# Hands_free_Motordrive_V1.net
KiCad netlist of a schematic drawn in Altium Designer
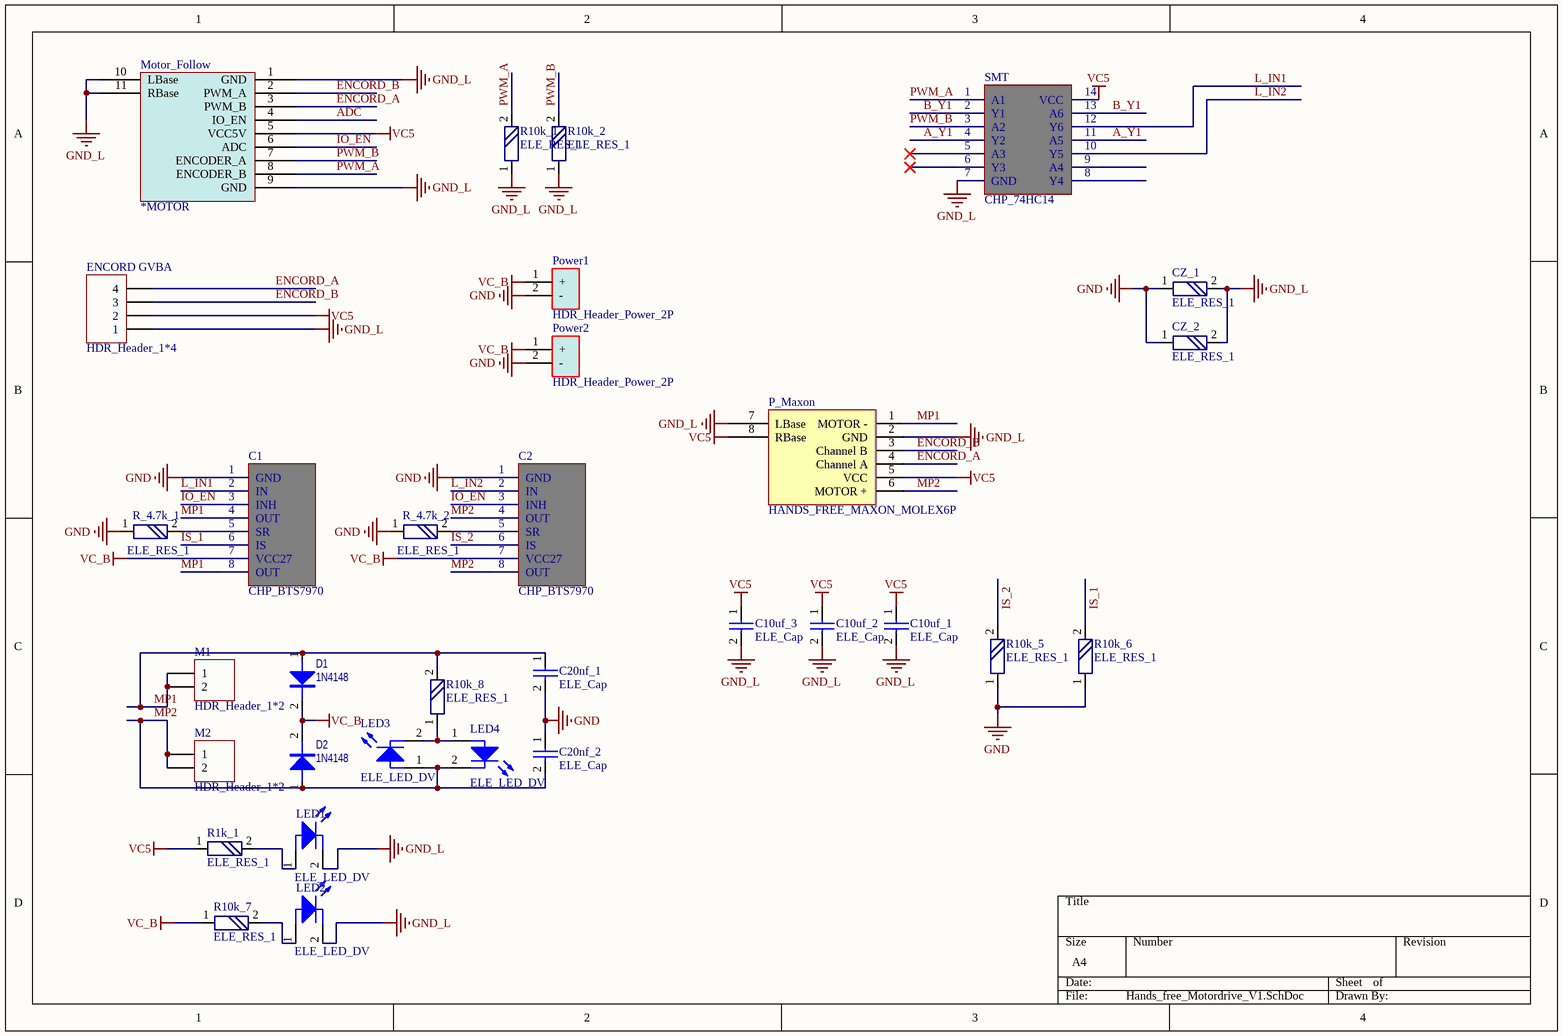
[diagram p0: Hands_free_Motordrive_V1.SchDoc]

(export (version "E")
  (design (tool "Eeschema 10.0.6"))
  (components
    (comp (ref "C1")
      (value "CHP_BTS7970")
      (footprint "CHP_BTS7970_P-TO-263_7")
      (libsource (lib "Hands_free") (part "CHP_BTS7970"))
    )
    (comp (ref "C2")
      (value "CHP_BTS7970")
      (footprint "CHP_BTS7970_P-TO-263_7")
      (libsource (lib "Hands_free") (part "CHP_BTS7970"))
    )
    (comp (ref "C10uf_1")
      (value "ELE_Cap")
      (footprint "ELE_0603_P")
      (description "电容")
      (libsource (lib "Hands_free") (part "ELE_Cap"))
    )
    (comp (ref "C10uf_2")
      (value "ELE_Cap")
      (footprint "ELE_0603_P")
      (description "电容")
      (libsource (lib "Hands_free") (part "ELE_Cap"))
    )
    (comp (ref "C10uf_3")
      (value "ELE_Cap")
      (footprint "ELE_0603_P")
      (description "电容")
      (libsource (lib "Hands_free") (part "ELE_Cap"))
    )
    (comp (ref "C20nf_1")
      (value "ELE_Cap")
      (footprint "ELE_0603_P")
      (description "电容")
      (libsource (lib "Hands_free") (part "ELE_Cap"))
    )
    (comp (ref "C20nf_2")
      (value "ELE_Cap")
      (footprint "ELE_0603_P")
      (description "电容")
      (libsource (lib "Hands_free") (part "ELE_Cap"))
    )
    (comp (ref "CZ_1")
      (value "ELE_RES_1")
      (footprint "ELE_0603_P")
      (description "电阻")
      (libsource (lib "Hands_free") (part "ELE_RES_1"))
    )
    (comp (ref "CZ_2")
      (value "ELE_RES_1")
      (footprint "ELE_0603_P")
      (description "电阻")
      (libsource (lib "Hands_free") (part "ELE_RES_1"))
    )
    (comp (ref "D1")
      (value "1N4148")
      (footprint "ELE_D1206")
      (description "二极管")
      (libsource (lib "Hands_free") (part "ELE_Diode"))
    )
    (comp (ref "D2")
      (value "1N4148")
      (footprint "ELE_D1206")
      (description "二极管")
      (libsource (lib "Hands_free") (part "ELE_Diode"))
    )
    (comp (ref "ENCORD GVBA")
      (value "HDR_Header_1*4")
      (footprint "HDR_Header_2.54_PH_1*4")
      (fields (field (name "PUBLISHER") "Altium Limited"))
      (libsource (lib "Hands_free") (part "HDR_Header_1*4"))
    )
    (comp (ref "LED1")
      (value "ELE_LED_DV")
      (footprint "ELE_LED_DV")
      (description "发光二极管 直插")
      (fields (field (name "PUBLISHER") "Altium Limited"))
      (libsource (lib "Hands_free") (part "ELE_LED_DV"))
    )
    (comp (ref "LED2")
      (value "ELE_LED_DV")
      (footprint "ELE_LED_DV")
      (description "发光二极管 直插")
      (fields (field (name "PUBLISHER") "Altium Limited"))
      (libsource (lib "Hands_free") (part "ELE_LED_DV"))
    )
    (comp (ref "LED3")
      (value "ELE_LED_DV")
      (footprint "ELE_LED_DV")
      (description "发光二极管 直插")
      (fields (field (name "PUBLISHER") "Altium Limited"))
      (libsource (lib "Hands_free") (part "ELE_LED_DV"))
    )
    (comp (ref "LED4")
      (value "ELE_LED_DV")
      (footprint "ELE_LED_DV")
      (description "发光二极管 直插")
      (fields (field (name "PUBLISHER") "Altium Limited"))
      (libsource (lib "Hands_free") (part "ELE_LED_DV"))
    )
    (comp (ref "M1")
      (value "HDR_Header_1*2")
      (footprint "HDR_H_PH_2P")
      (fields (field (name "PUBLISHER") "Altium Limited"))
      (libsource (lib "Hands_free") (part "HDR_Header_1*2"))
    )
    (comp (ref "M2")
      (value "HDR_Header_1*2")
      (footprint "HDR_H_PH_2P")
      (fields (field (name "PUBLISHER") "Altium Limited"))
      (libsource (lib "Hands_free") (part "HDR_Header_1*2"))
    )
    (comp (ref "Motor_Follow")
      (value "*MOTOR")
      (footprint "HDR_Molex_PH_1.25_9P")
      (libsource (lib "Hands_free") (part "HANDS_FREE_MOTOR"))
    )
    (comp (ref "Power1")
      (value "HDR_Header_Power_2P")
      (footprint "HDR_MOLEX_POWER5557_DH_2P")
      (libsource (lib "Hands_free") (part "HDR_Header_Power_2P"))
    )
    (comp (ref "Power2")
      (value "HDR_Header_Power_2P")
      (footprint "HDR_MOLEX_POWER5557_DH_2P")
      (libsource (lib "Hands_free") (part "HDR_Header_Power_2P"))
    )
    (comp (ref "P_Maxon")
      (value "HANDS_FREE_MAXON_MOLEX6P")
      (footprint "HDR_Molex_PH_1.25_6P")
      (libsource (lib "Hands_free") (part "HANDS_FREE_MAXON_MOLEX6P"))
    )
    (comp (ref "R1k_1")
      (value "ELE_RES_1")
      (footprint "ELE_0603_P")
      (description "电阻")
      (libsource (lib "Hands_free") (part "ELE_RES_1"))
    )
    (comp (ref "R10k_1")
      (value "ELE_RES_1")
      (footprint "ELE_0603_P")
      (description "电阻")
      (libsource (lib "Hands_free") (part "ELE_RES_1"))
    )
    (comp (ref "R10k_2")
      (value "ELE_RES_1")
      (footprint "ELE_0603_P")
      (description "电阻")
      (libsource (lib "Hands_free") (part "ELE_RES_1"))
    )
    (comp (ref "R10k_5")
      (value "ELE_RES_1")
      (footprint "ELE_0603_P")
      (description "电阻")
      (libsource (lib "Hands_free") (part "ELE_RES_1"))
    )
    (comp (ref "R10k_6")
      (value "ELE_RES_1")
      (footprint "ELE_0603_P")
      (description "电阻")
      (libsource (lib "Hands_free") (part "ELE_RES_1"))
    )
    (comp (ref "R10k_7")
      (value "ELE_RES_1")
      (footprint "ELE_0603_P")
      (description "电阻")
      (libsource (lib "Hands_free") (part "ELE_RES_1"))
    )
    (comp (ref "R10k_8")
      (value "ELE_RES_1")
      (footprint "ELE_0603_P")
      (description "电阻")
      (libsource (lib "Hands_free") (part "ELE_RES_1"))
    )
    (comp (ref "R_4.7k_1")
      (value "ELE_RES_1")
      (footprint "ELE_0603_P")
      (description "电阻")
      (libsource (lib "Hands_free") (part "ELE_RES_1"))
    )
    (comp (ref "R_4.7k_2")
      (value "ELE_RES_1")
      (footprint "ELE_0603_P")
      (description "电阻")
      (libsource (lib "Hands_free") (part "ELE_RES_1"))
    )
    (comp (ref "SMT")
      (value "CHP_74HC14")
      (footprint "CHP_SOP_14P")
      (description "反相施密特 7输入 SOP14")
      (libsource (lib "Hands_free") (part "CHP_74HC14"))
    )
  )
  (nets
    (net (code "1") (name "/ADC") (class "Default")
      (node (ref "Motor_Follow") (pin "4") (pinfunction "IO_EN_4") (pintype "passive"))
    )
    (net (code "2") (name "/A_Y1") (class "Default")
      (node (ref "SMT") (pin "11") (pinfunction "A5_11") (pintype "passive"))
      (node (ref "SMT") (pin "4") (pinfunction "Y2_4") (pintype "passive"))
    )
    (net (code "3") (name "/B_Y1") (class "Default")
      (node (ref "SMT") (pin "13") (pinfunction "A6_13") (pintype "passive"))
      (node (ref "SMT") (pin "2") (pinfunction "Y1_2") (pintype "passive"))
    )
    (net (code "4") (name "/ENCORD_A") (class "Default")
      (node (ref "ENCORD GVBA") (pin "4") (pinfunction "4_4") (pintype "passive"))
      (node (ref "Motor_Follow") (pin "3") (pinfunction "PWM_B_3") (pintype "passive"))
      (node (ref "P_Maxon") (pin "4") (pinfunction "Channel_A_4") (pintype "passive"))
    )
    (net (code "5") (name "/ENCORD_B") (class "Default")
      (node (ref "ENCORD GVBA") (pin "3") (pinfunction "3_3") (pintype "passive"))
      (node (ref "Motor_Follow") (pin "2") (pinfunction "PWM_A_2") (pintype "passive"))
      (node (ref "P_Maxon") (pin "3") (pinfunction "Channel_B_3") (pintype "passive"))
    )
    (net (code "6") (name "/IO_EN") (class "Default")
      (node (ref "C1") (pin "3") (pinfunction "INH_3") (pintype "passive"))
      (node (ref "C2") (pin "3") (pinfunction "INH_3") (pintype "passive"))
      (node (ref "Motor_Follow") (pin "6") (pinfunction "ADC_6") (pintype "passive"))
    )
    (net (code "7") (name "/IS_1") (class "Default")
      (node (ref "C1") (pin "6") (pinfunction "IS_6") (pintype "passive"))
      (node (ref "R10k_6") (pin "2") (pintype "passive"))
    )
    (net (code "8") (name "/IS_2") (class "Default")
      (node (ref "C2") (pin "6") (pinfunction "IS_6") (pintype "passive"))
      (node (ref "R10k_5") (pin "2") (pintype "passive"))
    )
    (net (code "9") (name "/L_IN1") (class "Default")
      (node (ref "C1") (pin "2") (pinfunction "IN_2") (pintype "passive"))
      (node (ref "SMT") (pin "12") (pinfunction "Y6_12") (pintype "passive"))
    )
    (net (code "10") (name "/L_IN2") (class "Default")
      (node (ref "C2") (pin "2") (pinfunction "IN_2") (pintype "passive"))
      (node (ref "SMT") (pin "10") (pinfunction "Y5_10") (pintype "passive"))
    )
    (net (code "11") (name "/MP1") (class "Default")
      (node (ref "C1") (pin "4") (pinfunction "OUT_4") (pintype "passive"))
      (node (ref "C1") (pin "8") (pinfunction "OUT_8") (pintype "passive"))
      (node (ref "C20nf_1") (pin "1") (pintype "passive"))
      (node (ref "D1") (pin "1") (pintype "passive"))
      (node (ref "M1") (pin "1") (pinfunction "1_1") (pintype "passive"))
      (node (ref "M1") (pin "2") (pinfunction "2_2") (pintype "passive"))
      (node (ref "P_Maxon") (pin "1") (pinfunction "MOTOR_-_1") (pintype "passive"))
      (node (ref "R10k_8") (pin "2") (pintype "passive"))
    )
    (net (code "12") (name "/MP2") (class "Default")
      (node (ref "C2") (pin "4") (pinfunction "OUT_4") (pintype "passive"))
      (node (ref "C2") (pin "8") (pinfunction "OUT_8") (pintype "passive"))
      (node (ref "C20nf_2") (pin "2") (pintype "passive"))
      (node (ref "D2") (pin "1") (pintype "passive"))
      (node (ref "LED3") (pin "1") (pintype "passive"))
      (node (ref "LED4") (pin "2") (pintype "passive"))
      (node (ref "M2") (pin "1") (pinfunction "1_1") (pintype "passive"))
      (node (ref "M2") (pin "2") (pinfunction "2_2") (pintype "passive"))
      (node (ref "P_Maxon") (pin "6") (pinfunction "MOTOR_+_6") (pintype "passive"))
    )
    (net (code "13") (name "/PWM_A") (class "Default")
      (node (ref "Motor_Follow") (pin "8") (pinfunction "ENCODER_B_8") (pintype "passive"))
      (node (ref "R10k_1") (pin "2") (pintype "passive"))
      (node (ref "SMT") (pin "1") (pinfunction "A1_1") (pintype "passive"))
    )
    (net (code "14") (name "/PWM_B") (class "Default")
      (node (ref "Motor_Follow") (pin "7") (pinfunction "ENCODER_A_7") (pintype "passive"))
      (node (ref "R10k_2") (pin "2") (pintype "passive"))
      (node (ref "SMT") (pin "3") (pinfunction "A2_3") (pintype "passive"))
    )
    (net (code "15") (name "GND") (class "Default")
      (node (ref "C1") (pin "1") (pinfunction "GND_1") (pintype "passive"))
      (node (ref "C2") (pin "1") (pinfunction "GND_1") (pintype "passive"))
      (node (ref "C20nf_1") (pin "2") (pintype "passive"))
      (node (ref "C20nf_2") (pin "1") (pintype "passive"))
      (node (ref "CZ_1") (pin "1") (pintype "passive"))
      (node (ref "CZ_2") (pin "1") (pintype "passive"))
      (node (ref "Power1") (pin "2") (pinfunction "-_2") (pintype "passive"))
      (node (ref "Power2") (pin "2") (pinfunction "-_2") (pintype "passive"))
      (node (ref "R10k_5") (pin "1") (pintype "passive"))
      (node (ref "R10k_6") (pin "1") (pintype "passive"))
      (node (ref "R_4.7k_1") (pin "1") (pintype "passive"))
      (node (ref "R_4.7k_2") (pin "1") (pintype "passive"))
    )
    (net (code "16") (name "GND_L") (class "Default")
      (node (ref "C10uf_1") (pin "2") (pintype "passive"))
      (node (ref "C10uf_2") (pin "2") (pintype "passive"))
      (node (ref "C10uf_3") (pin "2") (pintype "passive"))
      (node (ref "CZ_1") (pin "2") (pintype "passive"))
      (node (ref "CZ_2") (pin "2") (pintype "passive"))
      (node (ref "ENCORD GVBA") (pin "1") (pinfunction "1_1") (pintype "passive"))
      (node (ref "LED1") (pin "2") (pintype "passive"))
      (node (ref "LED2") (pin "2") (pintype "passive"))
      (node (ref "Motor_Follow") (pin "1") (pinfunction "GND_1") (pintype "passive"))
      (node (ref "Motor_Follow") (pin "10") (pinfunction "LBase_10") (pintype "passive"))
      (node (ref "Motor_Follow") (pin "11") (pinfunction "RBase_11") (pintype "passive"))
      (node (ref "Motor_Follow") (pin "9") (pinfunction "GND_9") (pintype "passive"))
      (node (ref "P_Maxon") (pin "2") (pinfunction "GND_2") (pintype "passive"))
      (node (ref "P_Maxon") (pin "7") (pinfunction "LBase_7") (pintype "passive"))
      (node (ref "R10k_1") (pin "1") (pintype "passive"))
      (node (ref "R10k_2") (pin "1") (pintype "passive"))
      (node (ref "SMT") (pin "7") (pinfunction "GND_7") (pintype "passive"))
    )
    (net (code "17") (name "Net-(C1-SR)") (class "Default")
      (node (ref "C1") (pin "5") (pinfunction "SR_5") (pintype "passive"))
      (node (ref "R_4.7k_1") (pin "2") (pintype "passive"))
    )
    (net (code "18") (name "Net-(C2-SR)") (class "Default")
      (node (ref "C2") (pin "5") (pinfunction "SR_5") (pintype "passive"))
      (node (ref "R_4.7k_2") (pin "2") (pintype "passive"))
    )
    (net (code "19") (name "Net-(LED1-Pad1)") (class "Default")
      (node (ref "LED1") (pin "1") (pintype "passive"))
      (node (ref "R1k_1") (pin "2") (pintype "passive"))
    )
    (net (code "20") (name "Net-(LED2-Pad1)") (class "Default")
      (node (ref "LED2") (pin "1") (pintype "passive"))
      (node (ref "R10k_7") (pin "2") (pintype "passive"))
    )
    (net (code "21") (name "Net-(LED3-Pad2)") (class "Default")
      (node (ref "LED3") (pin "2") (pintype "passive"))
      (node (ref "LED4") (pin "1") (pintype "passive"))
      (node (ref "R10k_8") (pin "1") (pintype "passive"))
    )
    (net (code "22") (name "VC5") (class "Default")
      (node (ref "C10uf_1") (pin "1") (pintype "passive"))
      (node (ref "C10uf_2") (pin "1") (pintype "passive"))
      (node (ref "C10uf_3") (pin "1") (pintype "passive"))
      (node (ref "ENCORD GVBA") (pin "2") (pinfunction "2_2") (pintype "passive"))
      (node (ref "Motor_Follow") (pin "5") (pinfunction "VCC5V_5") (pintype "passive"))
      (node (ref "P_Maxon") (pin "5") (pinfunction "VCC_5") (pintype "passive"))
      (node (ref "P_Maxon") (pin "8") (pinfunction "RBase_8") (pintype "passive"))
      (node (ref "R1k_1") (pin "1") (pintype "passive"))
      (node (ref "SMT") (pin "14") (pinfunction "VCC_14") (pintype "passive"))
    )
    (net (code "23") (name "VC_B") (class "Default")
      (node (ref "C1") (pin "7") (pinfunction "VCC27_7") (pintype "passive"))
      (node (ref "C2") (pin "7") (pinfunction "VCC27_7") (pintype "passive"))
      (node (ref "D1") (pin "2") (pintype "passive"))
      (node (ref "D2") (pin "2") (pintype "passive"))
      (node (ref "Power1") (pin "1") (pinfunction "+_1") (pintype "passive"))
      (node (ref "Power2") (pin "1") (pinfunction "+_1") (pintype "passive"))
      (node (ref "R10k_7") (pin "1") (pintype "passive"))
    )
    (net (code "24") (name "unconnected-(SMT-A3-Pad5)") (class "Default")
      (node (ref "SMT") (pin "5") (pinfunction "A3_5") (pintype "passive+no_connect"))
    )
    (net (code "25") (name "unconnected-(SMT-A4-Pad9)") (class "Default")
      (node (ref "SMT") (pin "9") (pinfunction "A4_9") (pintype "passive"))
    )
    (net (code "26") (name "unconnected-(SMT-Y3-Pad6)") (class "Default")
      (node (ref "SMT") (pin "6") (pinfunction "Y3_6") (pintype "passive+no_connect"))
    )
    (net (code "27") (name "unconnected-(SMT-Y4-Pad8)") (class "Default")
      (node (ref "SMT") (pin "8") (pinfunction "Y4_8") (pintype "passive"))
    )
  )
)
